# Peripheral.net
KiCad netlist of a schematic drawn in Altium Designer
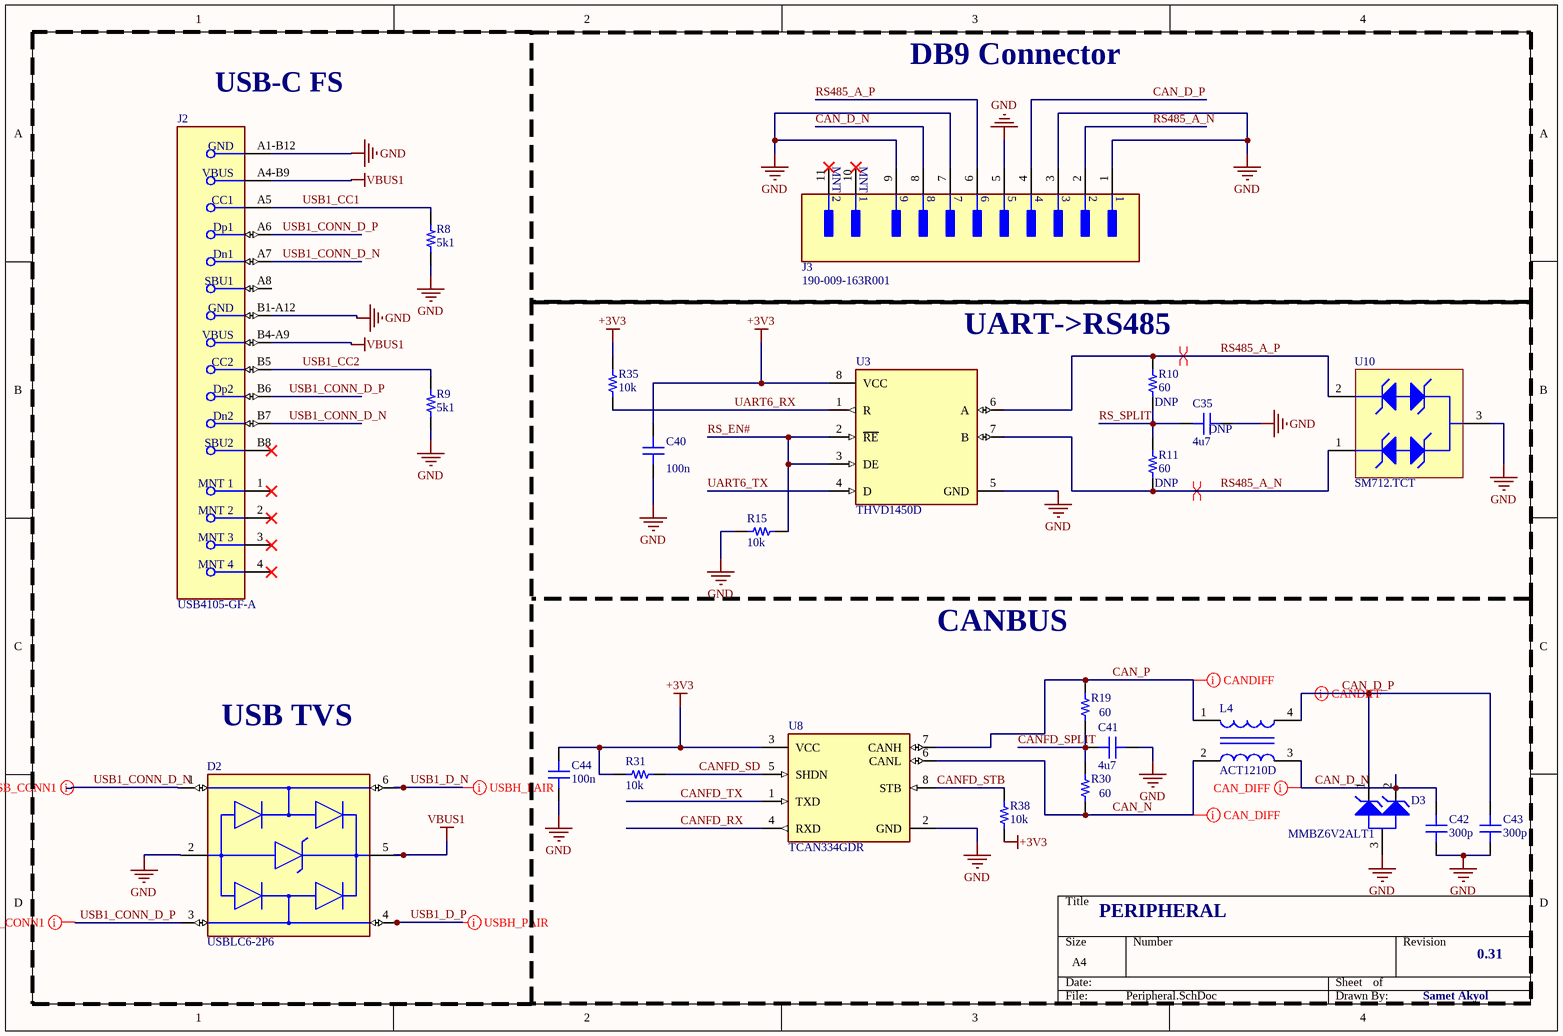
[diagram p0: Peripheral.SchDoc]

(export (version "E")
  (design (tool "Eeschema 10.0.6"))
  (components
    (comp (ref "C35")
      (value "DNP")
      (footprint "CAP 0402_1005")
      (description "CAP CER 4.7UF 4V X6S 0402")
      (fields
        (field (name "PART NUMBER") "C1005X6S0G475M050BC")
        (field (name "ALTIUM_VALUE") "4u7")
        (field (name "MANUFACTURER") "TDK Corporation")
      )
      (libsource (lib "Celestial Altium Library - altium_library") (part "Capacitor"))
    )
    (comp (ref "C40")
      (value "100n")
      (footprint "CAP 0402_1005")
      (description "CAP CER 0.1UF 4V X6S 0402")
      (fields
        (field (name "PART NUMBER") "C1005X6S0G475M050BC")
        (field (name "MANUFACTURER") "TDK Corporation")
      )
      (libsource (lib "Celestial Altium Library - altium_library") (part "Capacitor"))
    )
    (comp (ref "C41")
      (value "4u7")
      (footprint "CAP 0402_1005")
      (description "CAP CER 100NF 10V X7R 0402")
      (fields
        (field (name "PART NUMBER") "CL05B104KP5VPNC")
        (field (name "MANUFACTURER") "Samsung Electro-Mechanics")
      )
      (libsource (lib "Celestial Altium Library - altium_library") (part "Capacitor"))
    )
    (comp (ref "C42")
      (value "300p")
      (footprint "CAP 0402_1005")
      (description "CAP CER 100NF 10V X7R 0402")
      (fields
        (field (name "PART NUMBER") "CL05B104KP5VPNC")
        (field (name "MANUFACTURER") "Samsung Electro-Mechanics")
      )
      (libsource (lib "Celestial Altium Library - altium_library") (part "Capacitor"))
    )
    (comp (ref "C43")
      (value "300p")
      (footprint "CAP 0402_1005")
      (description "CAP CER 100NF 10V X7R 0402")
      (fields
        (field (name "PART NUMBER") "CL05B104KP5VPNC")
        (field (name "MANUFACTURER") "Samsung Electro-Mechanics")
      )
      (libsource (lib "Celestial Altium Library - altium_library") (part "Capacitor"))
    )
    (comp (ref "C44")
      (value "100n")
      (footprint "CAP 0402_1005")
      (description "CAP CER 100NF 10V X7R 0402")
      (fields
        (field (name "PART NUMBER") "CL05B104KP5VPNC")
        (field (name "MANUFACTURER") "Samsung Electro-Mechanics")
      )
      (libsource (lib "Celestial Altium Library - altium_library") (part "Capacitor"))
    )
    (comp (ref "D2")
      (value "USBLC6-2P6")
      (footprint "FP-SOT-666-MFG")
      (description "TVS DIODE 5.25V 17V SOT666")
      (libsource (lib "Altium Content Vault") (part "c871e55f7e3243d341edbd671b98d92"))
    )
    (comp (ref "D3")
      (value "MMBZ6V2ALT1")
      (footprint "ONSC-SOT-23-3-318-08_V")
      (fields (field (name "MANUFACTURER") "On Semiconductor"))
      (libsource (lib "Altium Content Vault") (part "ONSC-K1K2A3-3"))
    )
    (comp (ref "J2")
      (value "USB4105-GF-A")
      (footprint "FP-USB4105-GF-A-MFG")
      (description "CONN RCPT USB2.0 TYPEC 5A")
      (fields
        (field (name "MANUFACTURER") "GCT")
        (field (name "OCTOPART") "https://octopart.com/usb4105-gf-a-gct-106627878")
      )
      (libsource (lib "Altium Content Vault") (part "e7c17a616881a82b79941196b4bec10"))
    )
    (comp (ref "J3")
      (value "190-009-163R001")
      (footprint "FP-190-009-163R001-MFG")
      (description "190-009-163R001 D Type Connector, 9 Contact(s), Male, 0.109 inch Pitch, Solder Terminal, #4-40")
      (libsource (lib "Altium Content Vault") (part "bfa5909cba9379cb733595b161c4dbd"))
    )
    (comp (ref "L4")
      (value "ACT1210D")
      (footprint "FP-ACT1210D-MFG")
      (description "CMC 100UH 150MA 2LN SMD AEC-Q200")
      (libsource (lib "Altium Content Vault") (part "89d866506426b04047514f8507e1109"))
    )
    (comp (ref "R8")
      (value "5k1")
      (footprint "RES 0402_1005")
      (description "RES SMD 1K OHM 0.1% 1/16W 0402")
      (fields
        (field (name "PART NUMBER") "CPF0402B1K0E")
        (field (name "MANUFACTURER") "TE Connectivity Passive Product")
      )
      (libsource (lib "Celestial Altium Library - altium_library") (part "Resistor"))
    )
    (comp (ref "R9")
      (value "5k1")
      (footprint "RES 0402_1005")
      (description "RES SMD 1K OHM 0.1% 1/16W 0402")
      (fields
        (field (name "PART NUMBER") "CPF0402B1K0E")
        (field (name "MANUFACTURER") "TE Connectivity Passive Product")
      )
      (libsource (lib "Celestial Altium Library - altium_library") (part "Resistor"))
    )
    (comp (ref "R10")
      (value "DNP")
      (footprint "RES 0402_1005")
      (description "RES 60 OHM 0.1% 1/10W 0402")
      (fields
        (field (name "PART NUMBER") "RP73PF1E10KBTD")
        (field (name "ALTIUM_VALUE") "60")
        (field (name "MANUFACTURER") "TE Connectivity Passive Product")
      )
      (libsource (lib "Celestial Altium Library - altium_library") (part "Resistor"))
    )
    (comp (ref "R11")
      (value "DNP")
      (footprint "RES 0402_1005")
      (description "RES 60 OHM 0.1% 1/10W 0402")
      (fields
        (field (name "PART NUMBER") "RP73PF1E10KBTD")
        (field (name "ALTIUM_VALUE") "60")
        (field (name "MANUFACTURER") "TE Connectivity Passive Product")
      )
      (libsource (lib "Celestial Altium Library - altium_library") (part "Resistor"))
    )
    (comp (ref "R15")
      (value "10k")
      (footprint "RES 0402_1005")
      (description "RES 10K OHM 0.1% 1/10W 0402")
      (fields
        (field (name "PART NUMBER") "RP73PF1E10KBTD")
        (field (name "MANUFACTURER") "TE Connectivity Passive Product")
      )
      (libsource (lib "Celestial Altium Library - altium_library") (part "Resistor"))
    )
    (comp (ref "R19")
      (value "60")
      (footprint "RES 0402_1005")
      (description "RES 10K OHM 0.1% 1/10W 0402")
      (fields
        (field (name "PART NUMBER") "RP73PF1E10KBTD")
        (field (name "MANUFACTURER") "TE Connectivity Passive Product")
      )
      (libsource (lib "Celestial Altium Library - altium_library") (part "Resistor"))
    )
    (comp (ref "R30")
      (value "60")
      (footprint "RES 0402_1005")
      (description "RES 10K OHM 0.1% 1/10W 0402")
      (fields
        (field (name "PART NUMBER") "RP73PF1E10KBTD")
        (field (name "MANUFACTURER") "TE Connectivity Passive Product")
      )
      (libsource (lib "Celestial Altium Library - altium_library") (part "Resistor"))
    )
    (comp (ref "R31")
      (value "10k")
      (footprint "RES 0402_1005")
      (description "RES 10K OHM 0.1% 1/10W 0402")
      (fields
        (field (name "PART NUMBER") "RP73PF1E10KBTD")
        (field (name "MANUFACTURER") "TE Connectivity Passive Product")
      )
      (libsource (lib "Celestial Altium Library - altium_library") (part "Resistor"))
    )
    (comp (ref "R35")
      (value "10k")
      (footprint "RES 0402_1005")
      (description "RES 60 OHM 0.1% 1/10W 0402")
      (fields
        (field (name "PART NUMBER") "RP73PF1E10KBTD")
        (field (name "MANUFACTURER") "TE Connectivity Passive Product")
      )
      (libsource (lib "Celestial Altium Library - altium_library") (part "Resistor"))
    )
    (comp (ref "R38")
      (value "10k")
      (footprint "RES 0402_1005")
      (description "RES 10K OHM 0.1% 1/10W 0402")
      (fields
        (field (name "PART NUMBER") "RP73PF1E10KBTD")
        (field (name "MANUFACTURER") "TE Connectivity Passive Product")
      )
      (libsource (lib "Celestial Altium Library - altium_library") (part "Resistor"))
    )
    (comp (ref "U3")
      (value "THVD1450D")
      (footprint "FP-D0008A-IPC_B")
      (description "IC TRANSCEIVER HALF 1/1 8SOIC")
      (libsource (lib "Altium Content Vault") (part "1ad797bd8128b93b7a030b0c7bb8498"))
    )
    (comp (ref "U8")
      (value "TCAN334GDR")
      (footprint "FP-D0008A-IPC_B")
      (description "IC TRANSCEIVER 1/1 8SOIC")
      (libsource (lib "Altium Content Vault") (part "5621f34e3963f16c2984a53bd88c479"))
    )
    (comp (ref "U10")
      (value "SM712.TCT")
      (footprint "SMTC-SOT23-3_V")
      (fields (field (name "MANUFACTURER") "Semtech"))
      (libsource (lib "Altium Content Vault") (part "SMTC-SM712.TCT-SOT23-3"))
    )
  )
  (nets
    (net (code "1") (name "+3V3") (class "Default")
      (node (ref "C40") (pin "1") (pinfunction "1_1") (pintype "passive"))
      (node (ref "C44") (pin "1") (pinfunction "1_1") (pintype "passive"))
      (node (ref "R31") (pin "2") (pinfunction "2_2") (pintype "passive"))
      (node (ref "R35") (pin "2") (pinfunction "2_2") (pintype "passive"))
      (node (ref "R38") (pin "2") (pinfunction "2_2") (pintype "passive"))
      (node (ref "U3") (pin "8") (pinfunction "VCC_8") (pintype "power_in"))
      (node (ref "U8") (pin "3") (pinfunction "VCC_3") (pintype "power_in"))
    )
    (net (code "2") (name "/CANFD_RX") (class "Default")
      (node (ref "U8") (pin "4") (pinfunction "RXD_4") (pintype "output"))
    )
    (net (code "3") (name "/CANFD_SD") (class "Default")
      (node (ref "R31") (pin "1") (pinfunction "1_1") (pintype "passive"))
      (node (ref "U8") (pin "5") (pinfunction "SHDN_5") (pintype "input"))
    )
    (net (code "4") (name "/CANFD_SPLIT") (class "Default")
      (node (ref "C41") (pin "2") (pinfunction "2_2") (pintype "passive"))
      (node (ref "R19") (pin "1") (pinfunction "1_1") (pintype "passive"))
      (node (ref "R30") (pin "2") (pinfunction "2_2") (pintype "passive"))
    )
    (net (code "5") (name "/CANFD_STB") (class "Default")
      (node (ref "R38") (pin "1") (pinfunction "1_1") (pintype "passive"))
      (node (ref "U8") (pin "8") (pinfunction "STB_8") (pintype "input"))
    )
    (net (code "6") (name "/CANFD_TX") (class "Default")
      (node (ref "U8") (pin "1") (pinfunction "TXD_1") (pintype "input"))
    )
    (net (code "7") (name "/CAN_D_N") (class "Default")
      (node (ref "C42") (pin "2") (pinfunction "2_2") (pintype "passive"))
      (node (ref "D3") (pin "2") (pinfunction "K2_2") (pintype "passive"))
      (node (ref "J3") (pin "8") (pinfunction "8_8") (pintype "passive"))
      (node (ref "L4") (pin "3") (pinfunction "3_3") (pintype "passive"))
    )
    (net (code "8") (name "/CAN_D_P") (class "Default")
      (node (ref "C43") (pin "2") (pinfunction "2_2") (pintype "passive"))
      (node (ref "D3") (pin "1") (pinfunction "K1_1") (pintype "passive"))
      (node (ref "J3") (pin "4") (pinfunction "4_4") (pintype "passive"))
      (node (ref "L4") (pin "4") (pinfunction "4_4") (pintype "passive"))
    )
    (net (code "9") (name "/CAN_N") (class "Default")
      (node (ref "L4") (pin "2") (pinfunction "2_2") (pintype "passive"))
      (node (ref "R30") (pin "1") (pinfunction "1_1") (pintype "passive"))
      (node (ref "U8") (pin "6") (pinfunction "CANL_6") (pintype "bidirectional"))
    )
    (net (code "10") (name "/CAN_P") (class "Default")
      (node (ref "L4") (pin "1") (pinfunction "1_1") (pintype "passive"))
      (node (ref "R19") (pin "2") (pinfunction "2_2") (pintype "passive"))
      (node (ref "U8") (pin "7") (pinfunction "CANH_7") (pintype "bidirectional"))
    )
    (net (code "11") (name "/RS485_A_N") (class "Default")
      (node (ref "J3") (pin "2") (pinfunction "2_2") (pintype "passive"))
      (node (ref "R11") (pin "1") (pinfunction "1_1") (pintype "passive"))
      (node (ref "U10") (pin "1") (pinfunction "1_1") (pintype "passive"))
      (node (ref "U3") (pin "7") (pinfunction "B_7") (pintype "bidirectional"))
    )
    (net (code "12") (name "/RS485_A_P") (class "Default")
      (node (ref "J3") (pin "6") (pinfunction "6_6") (pintype "passive"))
      (node (ref "R10") (pin "2") (pinfunction "2_2") (pintype "passive"))
      (node (ref "U10") (pin "2") (pinfunction "2_2") (pintype "passive"))
      (node (ref "U3") (pin "6") (pinfunction "A_6") (pintype "bidirectional"))
    )
    (net (code "13") (name "/RS_EN#") (class "Default")
      (node (ref "R15") (pin "1") (pinfunction "1_1") (pintype "passive"))
      (node (ref "U3") (pin "2") (pinfunction "~{RE}_2") (pintype "input"))
      (node (ref "U3") (pin "3") (pinfunction "DE_3") (pintype "input"))
    )
    (net (code "14") (name "/RS_SPLIT") (class "Default")
      (node (ref "C35") (pin "1") (pinfunction "1_1") (pintype "passive"))
      (node (ref "R10") (pin "1") (pinfunction "1_1") (pintype "passive"))
      (node (ref "R11") (pin "2") (pinfunction "2_2") (pintype "passive"))
    )
    (net (code "15") (name "/UART6_RX") (class "Default")
      (node (ref "R35") (pin "1") (pinfunction "1_1") (pintype "passive"))
      (node (ref "U3") (pin "1") (pinfunction "R_1") (pintype "output"))
    )
    (net (code "16") (name "/UART6_TX") (class "Default")
      (node (ref "U3") (pin "4") (pinfunction "D_4") (pintype "input"))
    )
    (net (code "17") (name "/USB1_CC1") (class "Default")
      (node (ref "J2") (pin "A5") (pinfunction "CC1_A5") (pintype "power_in"))
      (node (ref "R8") (pin "2") (pinfunction "2_2") (pintype "passive"))
    )
    (net (code "18") (name "/USB1_CC2") (class "Default")
      (node (ref "J2") (pin "B5") (pinfunction "CC2_B5") (pintype "bidirectional"))
      (node (ref "R9") (pin "2") (pinfunction "2_2") (pintype "passive"))
    )
    (net (code "19") (name "/USB1_CONN_D_N") (class "Default")
      (node (ref "D2") (pin "1") (pinfunction "I/O1_1") (pintype "bidirectional"))
      (node (ref "J2") (pin "A7") (pinfunction "Dn1_A7") (pintype "bidirectional"))
      (node (ref "J2") (pin "B7") (pinfunction "Dn2_B7") (pintype "bidirectional"))
    )
    (net (code "20") (name "/USB1_CONN_D_P") (class "Default")
      (node (ref "D2") (pin "3") (pinfunction "I/O2_3") (pintype "bidirectional"))
      (node (ref "J2") (pin "A6") (pinfunction "Dp1_A6") (pintype "bidirectional"))
      (node (ref "J2") (pin "B6") (pinfunction "Dp2_B6") (pintype "bidirectional"))
    )
    (net (code "21") (name "/USB1_D_N") (class "Default")
      (node (ref "D2") (pin "6") (pinfunction "I/O1_6") (pintype "bidirectional"))
    )
    (net (code "22") (name "/USB1_D_P") (class "Default")
      (node (ref "D2") (pin "4") (pinfunction "I/O2_4") (pintype "bidirectional"))
    )
    (net (code "23") (name "GND") (class "Default")
      (node (ref "C35") (pin "2") (pinfunction "2_2") (pintype "passive"))
      (node (ref "C40") (pin "2") (pinfunction "2_2") (pintype "passive"))
      (node (ref "C41") (pin "1") (pinfunction "1_1") (pintype "passive"))
      (node (ref "C42") (pin "1") (pinfunction "1_1") (pintype "passive"))
      (node (ref "C43") (pin "1") (pinfunction "1_1") (pintype "passive"))
      (node (ref "C44") (pin "2") (pinfunction "2_2") (pintype "passive"))
      (node (ref "D2") (pin "2") (pinfunction "GND_2") (pintype "power_in"))
      (node (ref "D3") (pin "3") (pinfunction "A_3") (pintype "passive"))
      (node (ref "J2") (pin "A1-B12") (pinfunction "GND_A1-B12") (pintype "power_in"))
      (node (ref "J2") (pin "B1-A12") (pinfunction "GND_B1-A12") (pintype "bidirectional"))
      (node (ref "J3") (pin "1") (pinfunction "1_1") (pintype "passive"))
      (node (ref "J3") (pin "3") (pinfunction "3_3") (pintype "passive"))
      (node (ref "J3") (pin "5") (pinfunction "5_5") (pintype "passive"))
      (node (ref "J3") (pin "7") (pinfunction "7_7") (pintype "passive"))
      (node (ref "J3") (pin "9") (pinfunction "9_9") (pintype "passive"))
      (node (ref "R15") (pin "2") (pinfunction "2_2") (pintype "passive"))
      (node (ref "R8") (pin "1") (pinfunction "1_1") (pintype "passive"))
      (node (ref "R9") (pin "1") (pinfunction "1_1") (pintype "passive"))
      (node (ref "U10") (pin "3") (pinfunction "3_3") (pintype "passive"))
      (node (ref "U3") (pin "5") (pinfunction "GND_5") (pintype "power_in"))
      (node (ref "U8") (pin "2") (pinfunction "GND_2") (pintype "power_in"))
    )
    (net (code "24") (name "VBUS1") (class "Default")
      (node (ref "D2") (pin "5") (pinfunction "VBUS_5") (pintype "power_in"))
      (node (ref "J2") (pin "A4-B9") (pinfunction "VBUS_A4-B9") (pintype "power_in"))
      (node (ref "J2") (pin "B4-A9") (pinfunction "VBUS_B4-A9") (pintype "bidirectional"))
    )
    (net (code "25") (name "unconnected-(J2-MNT_1-Pad1)") (class "Default")
      (node (ref "J2") (pin "1") (pinfunction "MNT_1_1") (pintype "power_in+no_connect"))
    )
    (net (code "26") (name "unconnected-(J2-MNT_2-Pad2)") (class "Default")
      (node (ref "J2") (pin "2") (pinfunction "MNT_2_2") (pintype "power_in+no_connect"))
    )
    (net (code "27") (name "unconnected-(J2-MNT_3-Pad3)") (class "Default")
      (node (ref "J2") (pin "3") (pinfunction "MNT_3_3") (pintype "power_in+no_connect"))
    )
    (net (code "28") (name "unconnected-(J2-MNT_4-Pad4)") (class "Default")
      (node (ref "J2") (pin "4") (pinfunction "MNT_4_4") (pintype "power_in+no_connect"))
    )
    (net (code "29") (name "unconnected-(J2-SBU1-PadA8)") (class "Default")
      (node (ref "J2") (pin "A8") (pinfunction "SBU1_A8") (pintype "bidirectional"))
    )
    (net (code "30") (name "unconnected-(J2-SBU2-PadB8)") (class "Default")
      (node (ref "J2") (pin "B8") (pinfunction "SBU2_B8") (pintype "power_in+no_connect"))
    )
    (net (code "31") (name "unconnected-(J3-MNT_1-Pad10)") (class "Default")
      (node (ref "J3") (pin "10") (pinfunction "MNT_1_10") (pintype "passive+no_connect"))
    )
    (net (code "32") (name "unconnected-(J3-MNT_2-Pad11)") (class "Default")
      (node (ref "J3") (pin "11") (pinfunction "MNT_2_11") (pintype "passive+no_connect"))
    )
  )
)
